# CMoy-Pro-V_B1.net
KiCad netlist of a schematic drawn in EAGLE
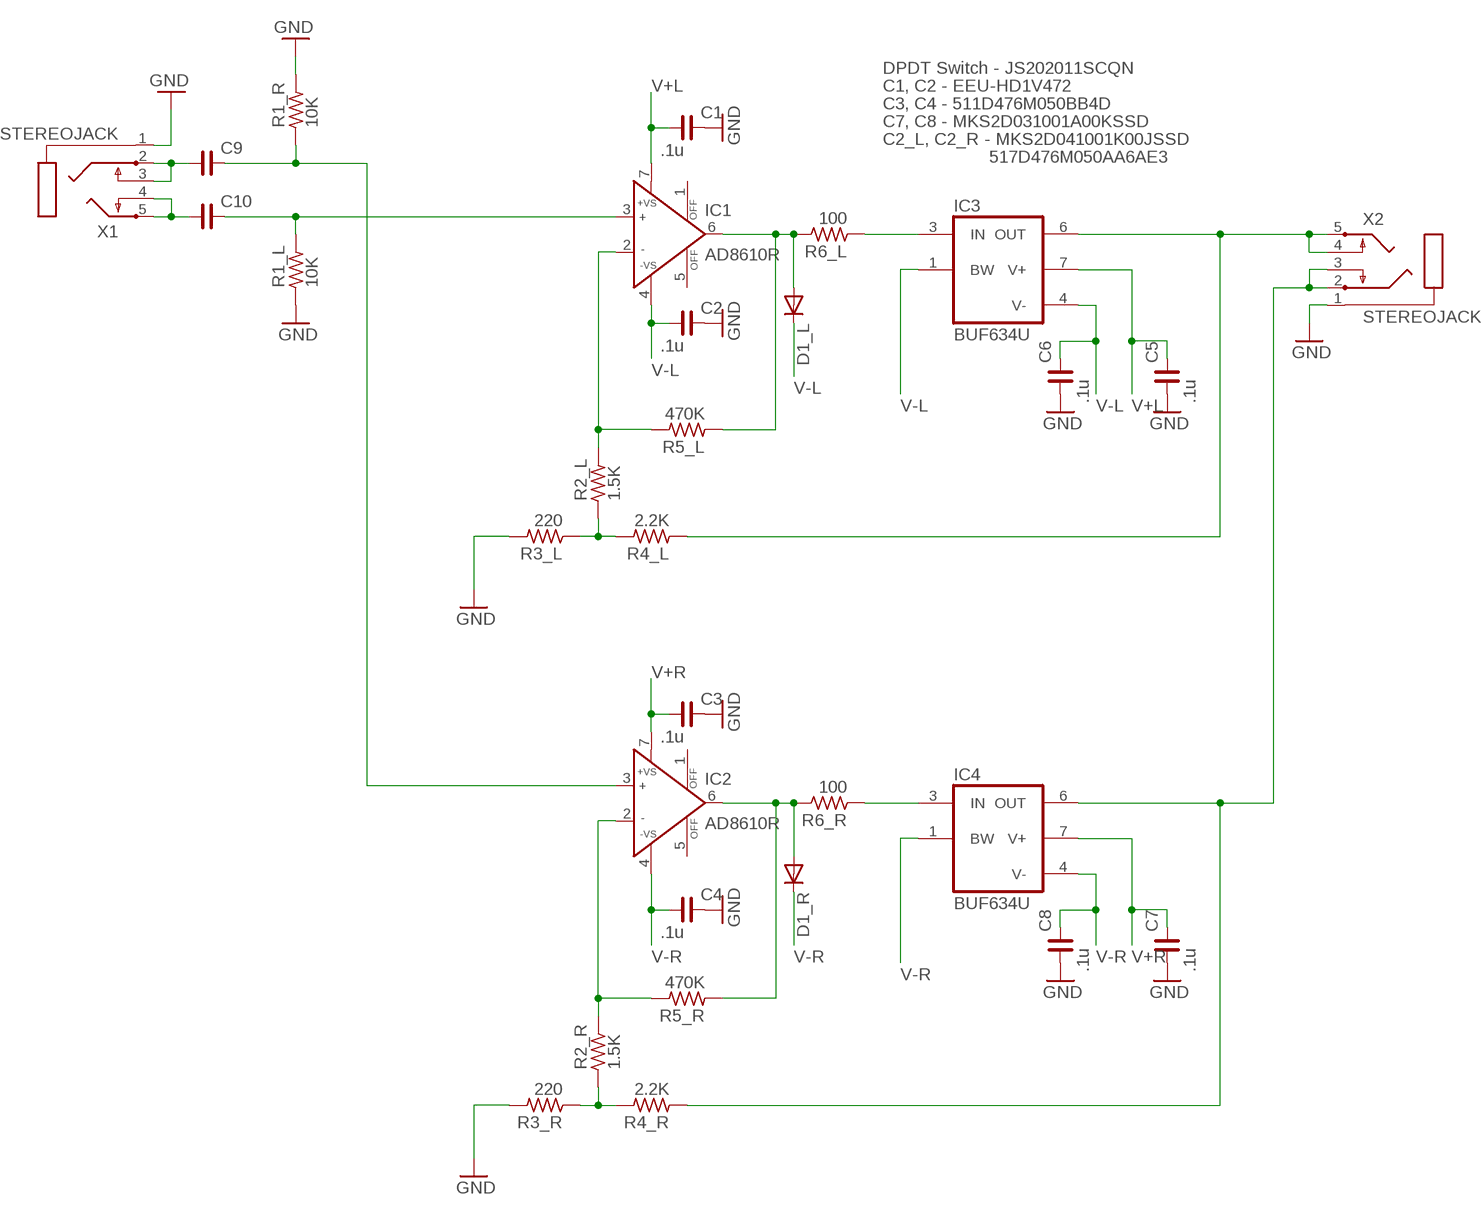
[diagram p0: schematic, sheet 1]

(export (version "E")
  (design (tool "Eeschema 10.0.6"))
  (components
    (comp (ref "C1")
      (value ".1u")
      (footprint "eagle-import:C0603")
      (libsource (lib "eagle-import") (part "C_0603"))
    )
    (comp (ref "C2")
      (value ".1u")
      (footprint "eagle-import:C0603")
      (libsource (lib "eagle-import") (part "C_0603"))
    )
    (comp (ref "C3")
      (value ".1u")
      (footprint "eagle-import:C0603")
      (libsource (lib "eagle-import") (part "C_0603"))
    )
    (comp (ref "C4")
      (value ".1u")
      (footprint "eagle-import:C0603")
      (libsource (lib "eagle-import") (part "C_0603"))
    )
    (comp (ref "C5")
      (value ".1u")
      (footprint "eagle-import:C0603")
      (libsource (lib "eagle-import") (part "C_0603"))
    )
    (comp (ref "C6")
      (value ".1u")
      (footprint "eagle-import:C0603")
      (libsource (lib "eagle-import") (part "C_0603"))
    )
    (comp (ref "C7")
      (value ".1u")
      (footprint "eagle-import:C0603")
      (libsource (lib "eagle-import") (part "C_0603"))
    )
    (comp (ref "C8")
      (value ".1u")
      (footprint "eagle-import:C0603")
      (libsource (lib "eagle-import") (part "C_0603"))
    )
    (comp (ref "C9")
      (value "C_1210")
      (footprint "eagle-import:C1210")
      (libsource (lib "eagle-import") (part "C_1210"))
    )
    (comp (ref "C10")
      (value "C_1210")
      (footprint "eagle-import:C1210")
      (libsource (lib "eagle-import") (part "C_1210"))
    )
    (comp (ref "D1_L")
      (value "DIODE-SOD-123")
      (footprint "eagle-import:SOD-123")
      (libsource (lib "eagle-import") (part "DIODE-SOD-123"))
    )
    (comp (ref "D1_R")
      (value "DIODE-SOD-123")
      (footprint "eagle-import:SOD-123")
      (libsource (lib "eagle-import") (part "DIODE-SOD-123"))
    )
    (comp (ref "IC1")
      (value "AD8610R")
      (footprint "eagle-import:SO8")
      (fields (field (name "MF") "ALTERA CORPORATION") (field (name "MPN") "AD8610BRZ"))
      (libsource (lib "eagle-import") (part "AD8610R"))
    )
    (comp (ref "IC2")
      (value "AD8610R")
      (footprint "eagle-import:SO8")
      (fields (field (name "MF") "ALTERA CORPORATION") (field (name "MPN") "AD8610BRZ"))
      (libsource (lib "eagle-import") (part "AD8610R"))
    )
    (comp (ref "IC3")
      (value "BUF634U")
      (footprint "eagle-import:SO08")
      (libsource (lib "eagle-import") (part "BUF634U"))
    )
    (comp (ref "IC4")
      (value "BUF634U")
      (footprint "eagle-import:SO08")
      (libsource (lib "eagle-import") (part "BUF634U"))
    )
    (comp (ref "R1_L")
      (value "10K")
      (footprint "eagle-import:R0805")
      (libsource (lib "eagle-import") (part "R_0805"))
    )
    (comp (ref "R1_R")
      (value "10K")
      (footprint "eagle-import:R0805")
      (libsource (lib "eagle-import") (part "R_0805"))
    )
    (comp (ref "R2_L")
      (value "1.5K")
      (footprint "eagle-import:R0805")
      (libsource (lib "eagle-import") (part "R_0805"))
    )
    (comp (ref "R2_R")
      (value "1.5K")
      (footprint "eagle-import:R0805")
      (libsource (lib "eagle-import") (part "R_0805"))
    )
    (comp (ref "R3_L")
      (value "220")
      (footprint "eagle-import:R0805")
      (libsource (lib "eagle-import") (part "R_0805"))
    )
    (comp (ref "R3_R")
      (value "220")
      (footprint "eagle-import:R0805")
      (libsource (lib "eagle-import") (part "R_0805"))
    )
    (comp (ref "R4_L")
      (value "2.2K")
      (footprint "eagle-import:R0805")
      (libsource (lib "eagle-import") (part "R_0805"))
    )
    (comp (ref "R4_R")
      (value "2.2K")
      (footprint "eagle-import:R0805")
      (libsource (lib "eagle-import") (part "R_0805"))
    )
    (comp (ref "R5_L")
      (value "470K")
      (footprint "eagle-import:R0805")
      (libsource (lib "eagle-import") (part "R_0805"))
    )
    (comp (ref "R5_R")
      (value "470K")
      (footprint "eagle-import:R0805")
      (libsource (lib "eagle-import") (part "R_0805"))
    )
    (comp (ref "R6_L")
      (value "100")
      (footprint "eagle-import:R0805")
      (libsource (lib "eagle-import") (part "R_0805"))
    )
    (comp (ref "R6_R")
      (value "100")
      (footprint "eagle-import:R0805")
      (libsource (lib "eagle-import") (part "R_0805"))
    )
    (comp (ref "X1")
      (value "STEREOJACK")
      (footprint "eagle-import:STX3100")
      (libsource (lib "eagle-import") (part "STEREOJACK"))
    )
    (comp (ref "X2")
      (value "STEREOJACK")
      (footprint "eagle-import:STX3100")
      (libsource (lib "eagle-import") (part "STEREOJACK"))
    )
  )
  (nets
    (net (code "1") (name "/V+L") (class "Default")
      (node (ref "C1") (pin "1") (pinfunction "1_1") (pintype "passive"))
      (node (ref "C5") (pin "2") (pinfunction "2_2") (pintype "passive"))
      (node (ref "IC1") (pin "7") (pinfunction "+VS_7") (pintype "input"))
      (node (ref "IC3") (pin "7") (pinfunction "V+_7") (pintype "power_in"))
    )
    (net (code "2") (name "/V+R") (class "Default")
      (node (ref "C3") (pin "1") (pinfunction "1_1") (pintype "passive"))
      (node (ref "C7") (pin "2") (pinfunction "2_2") (pintype "passive"))
      (node (ref "IC2") (pin "7") (pinfunction "+VS_7") (pintype "input"))
      (node (ref "IC4") (pin "7") (pinfunction "V+_7") (pintype "power_in"))
    )
    (net (code "3") (name "/V-L") (class "Default")
      (node (ref "C2") (pin "1") (pinfunction "1_1") (pintype "passive"))
      (node (ref "C6") (pin "2") (pinfunction "2_2") (pintype "passive"))
      (node (ref "D1_L") (pin "C") (pinfunction "C_C") (pintype "passive"))
      (node (ref "IC1") (pin "4") (pinfunction "-VS_4") (pintype "input"))
      (node (ref "IC3") (pin "1") (pinfunction "BW_1") (pintype "passive"))
      (node (ref "IC3") (pin "4") (pinfunction "V-_4") (pintype "power_in"))
    )
    (net (code "4") (name "/V-R") (class "Default")
      (node (ref "C4") (pin "1") (pinfunction "1_1") (pintype "passive"))
      (node (ref "C8") (pin "2") (pinfunction "2_2") (pintype "passive"))
      (node (ref "D1_R") (pin "C") (pinfunction "C_C") (pintype "passive"))
      (node (ref "IC2") (pin "4") (pinfunction "-VS_4") (pintype "input"))
      (node (ref "IC4") (pin "1") (pinfunction "BW_1") (pintype "passive"))
      (node (ref "IC4") (pin "4") (pinfunction "V-_4") (pintype "power_in"))
    )
    (net (code "5") (name "GND") (class "Default")
      (node (ref "C1") (pin "2") (pinfunction "2_2") (pintype "passive"))
      (node (ref "C2") (pin "2") (pinfunction "2_2") (pintype "passive"))
      (node (ref "C3") (pin "2") (pinfunction "2_2") (pintype "passive"))
      (node (ref "C4") (pin "2") (pinfunction "2_2") (pintype "passive"))
      (node (ref "C5") (pin "1") (pinfunction "1_1") (pintype "passive"))
      (node (ref "C6") (pin "1") (pinfunction "1_1") (pintype "passive"))
      (node (ref "C7") (pin "1") (pinfunction "1_1") (pintype "passive"))
      (node (ref "C8") (pin "1") (pinfunction "1_1") (pintype "passive"))
      (node (ref "R1_L") (pin "1") (pinfunction "1_1") (pintype "passive"))
      (node (ref "R1_R") (pin "2") (pinfunction "2_2") (pintype "passive"))
      (node (ref "R3_L") (pin "2") (pinfunction "2_2") (pintype "passive"))
      (node (ref "R3_R") (pin "2") (pinfunction "2_2") (pintype "passive"))
      (node (ref "X1") (pin "1") (pinfunction "1_1") (pintype "passive"))
      (node (ref "X2") (pin "1") (pinfunction "1_1") (pintype "passive"))
    )
    (net (code "6") (name "Net-(C9-Pad1)") (class "Default")
      (node (ref "C9") (pin "1") (pinfunction "1_1") (pintype "passive"))
      (node (ref "X1") (pin "2") (pinfunction "2_2") (pintype "passive"))
      (node (ref "X1") (pin "3") (pinfunction "3_3") (pintype "passive"))
    )
    (net (code "7") (name "Net-(C10-Pad1)") (class "Default")
      (node (ref "C10") (pin "1") (pinfunction "1_1") (pintype "passive"))
      (node (ref "X1") (pin "4") (pinfunction "4_4") (pintype "passive"))
      (node (ref "X1") (pin "5") (pinfunction "5_5") (pintype "passive"))
    )
    (net (code "8") (name "Net-(IC1-IN+)") (class "Default")
      (node (ref "C10") (pin "2") (pinfunction "2_2") (pintype "passive"))
      (node (ref "IC1") (pin "3") (pinfunction "IN+_3") (pintype "input"))
      (node (ref "R1_L") (pin "2") (pinfunction "2_2") (pintype "passive"))
    )
    (net (code "9") (name "Net-(IC1-IN-)") (class "Default")
      (node (ref "IC1") (pin "2") (pinfunction "IN-_2") (pintype "input"))
      (node (ref "R2_L") (pin "2") (pinfunction "2_2") (pintype "passive"))
      (node (ref "R5_L") (pin "2") (pinfunction "2_2") (pintype "passive"))
    )
    (net (code "10") (name "Net-(IC1-OUT)") (class "Default")
      (node (ref "D1_L") (pin "A") (pinfunction "A_A") (pintype "passive"))
      (node (ref "IC1") (pin "6") (pinfunction "OUT_6") (pintype "output"))
      (node (ref "R5_L") (pin "1") (pinfunction "1_1") (pintype "passive"))
      (node (ref "R6_L") (pin "2") (pinfunction "2_2") (pintype "passive"))
    )
    (net (code "11") (name "Net-(IC2-IN+)") (class "Default")
      (node (ref "C9") (pin "2") (pinfunction "2_2") (pintype "passive"))
      (node (ref "IC2") (pin "3") (pinfunction "IN+_3") (pintype "input"))
      (node (ref "R1_R") (pin "1") (pinfunction "1_1") (pintype "passive"))
    )
    (net (code "12") (name "Net-(IC2-IN-)") (class "Default")
      (node (ref "IC2") (pin "2") (pinfunction "IN-_2") (pintype "input"))
      (node (ref "R2_R") (pin "2") (pinfunction "2_2") (pintype "passive"))
      (node (ref "R5_R") (pin "2") (pinfunction "2_2") (pintype "passive"))
    )
    (net (code "13") (name "Net-(IC2-OUT)") (class "Default")
      (node (ref "D1_R") (pin "A") (pinfunction "A_A") (pintype "passive"))
      (node (ref "IC2") (pin "6") (pinfunction "OUT_6") (pintype "output"))
      (node (ref "R5_R") (pin "1") (pinfunction "1_1") (pintype "passive"))
      (node (ref "R6_R") (pin "2") (pinfunction "2_2") (pintype "passive"))
    )
    (net (code "14") (name "Net-(IC3-IN)") (class "Default")
      (node (ref "IC3") (pin "3") (pinfunction "IN_3") (pintype "input"))
      (node (ref "R6_L") (pin "1") (pinfunction "1_1") (pintype "passive"))
    )
    (net (code "15") (name "Net-(IC3-OUT)") (class "Default")
      (node (ref "IC3") (pin "6") (pinfunction "OUT_6") (pintype "output"))
      (node (ref "R4_L") (pin "1") (pinfunction "1_1") (pintype "passive"))
      (node (ref "X2") (pin "4") (pinfunction "4_4") (pintype "passive"))
      (node (ref "X2") (pin "5") (pinfunction "5_5") (pintype "passive"))
    )
    (net (code "16") (name "Net-(IC4-IN)") (class "Default")
      (node (ref "IC4") (pin "3") (pinfunction "IN_3") (pintype "input"))
      (node (ref "R6_R") (pin "1") (pinfunction "1_1") (pintype "passive"))
    )
    (net (code "17") (name "Net-(IC4-OUT)") (class "Default")
      (node (ref "IC4") (pin "6") (pinfunction "OUT_6") (pintype "output"))
      (node (ref "R4_R") (pin "1") (pinfunction "1_1") (pintype "passive"))
      (node (ref "X2") (pin "2") (pinfunction "2_2") (pintype "passive"))
      (node (ref "X2") (pin "3") (pinfunction "3_3") (pintype "passive"))
    )
    (net (code "18") (name "Net-(R2_L-Pad1)") (class "Default")
      (node (ref "R2_L") (pin "1") (pinfunction "1_1") (pintype "passive"))
      (node (ref "R3_L") (pin "1") (pinfunction "1_1") (pintype "passive"))
      (node (ref "R4_L") (pin "2") (pinfunction "2_2") (pintype "passive"))
    )
    (net (code "19") (name "Net-(R2_R-Pad1)") (class "Default")
      (node (ref "R2_R") (pin "1") (pinfunction "1_1") (pintype "passive"))
      (node (ref "R3_R") (pin "1") (pinfunction "1_1") (pintype "passive"))
      (node (ref "R4_R") (pin "2") (pinfunction "2_2") (pintype "passive"))
    )
    (net (code "20") (name "unconnected-(IC1-OFF-Pad1)") (class "Default")
      (node (ref "IC1") (pin "1") (pinfunction "OFF_1") (pintype "passive"))
    )
    (net (code "21") (name "unconnected-(IC1-OFF-Pad5)") (class "Default")
      (node (ref "IC1") (pin "5") (pinfunction "OFF_5") (pintype "passive"))
    )
    (net (code "22") (name "unconnected-(IC2-OFF-Pad1)") (class "Default")
      (node (ref "IC2") (pin "1") (pinfunction "OFF_1") (pintype "passive"))
    )
    (net (code "23") (name "unconnected-(IC2-OFF-Pad5)") (class "Default")
      (node (ref "IC2") (pin "5") (pinfunction "OFF_5") (pintype "passive"))
    )
  )
)
